# ELECTRONIC_LOAD.net
KiCad netlist of a schematic drawn in Altium Designer
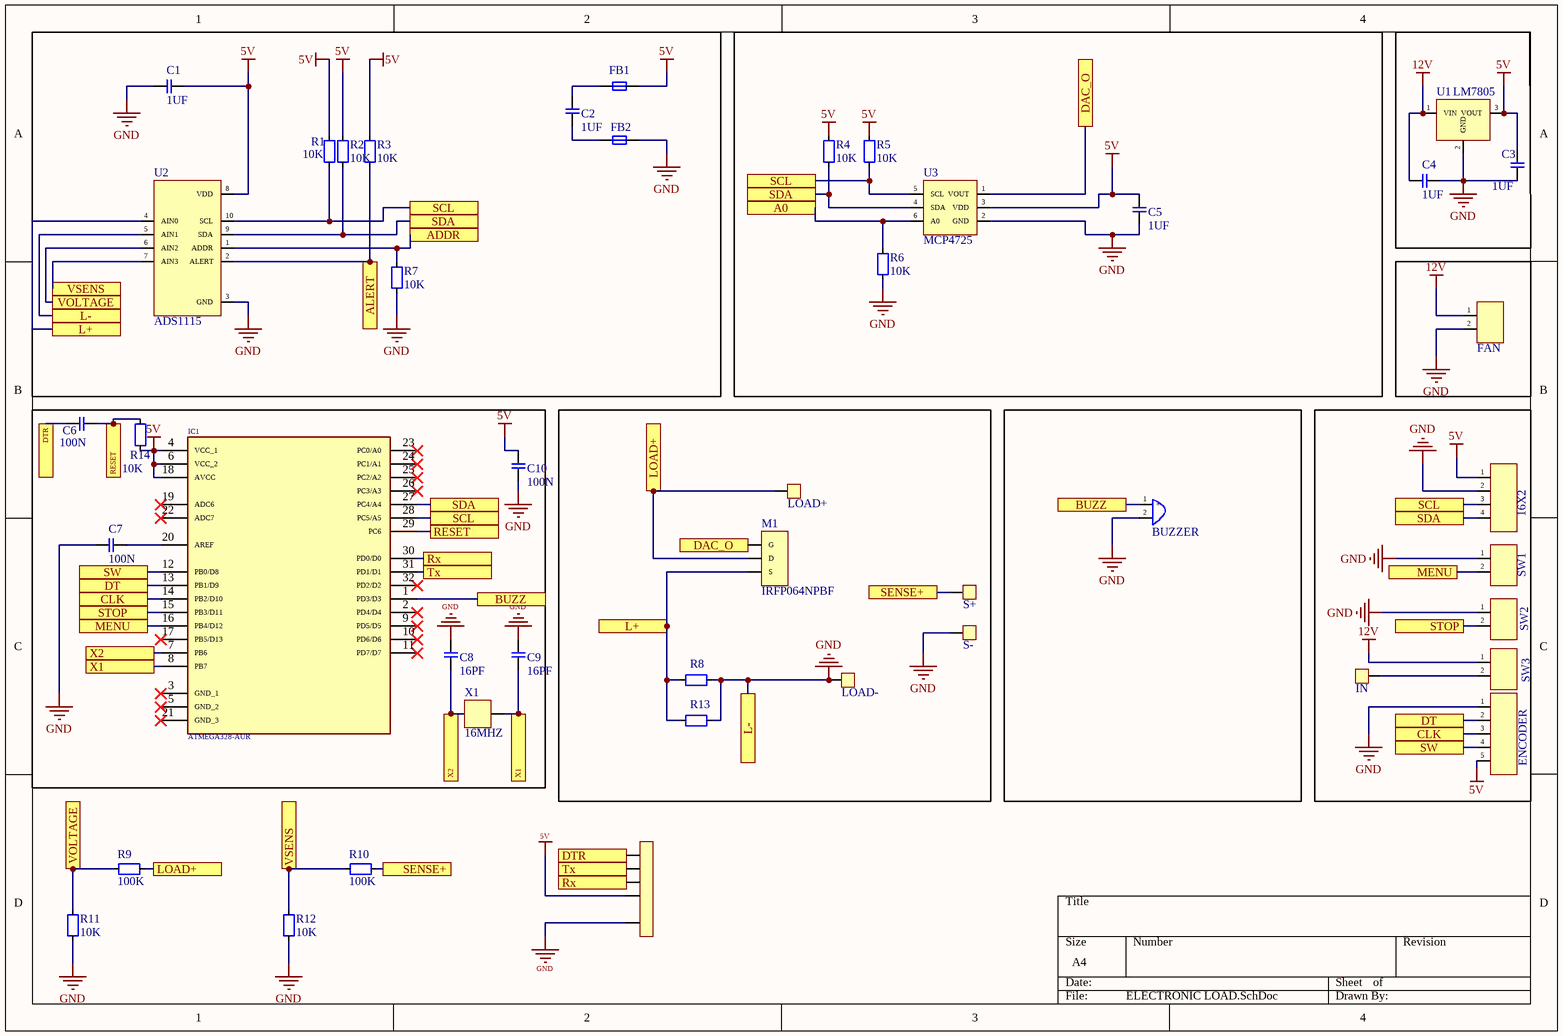
[diagram p0: ELECTRONIC LOAD.SchDoc]

(export (version "E")
  (design (tool "Eeschema 10.0.6"))
  (components
    (comp (ref "16X2") (value "16X2") (footprint "4PIN") (libsource (lib "ELECTRONIC LOAD") (part "4PIN")))
    (comp (ref "BUZZER")
      (value "BUZZER")
      (footprint "BUZZER")
      (description "YX-YT12075-YT03D")
      (libsource (lib "ELECTRONIC LOAD") (part "BUZZER"))
    )
    (comp (ref "C1")
      (value "1UF")
      (footprint "C-0805W")
      (description "0603 CAPACITOR")
      (libsource (lib "ELECTRONIC LOAD") (part "1UF CAPACITOR"))
    )
    (comp (ref "C2")
      (value "1UF")
      (footprint "C-0805W")
      (description "0603 CAPACITOR")
      (libsource (lib "ELECTRONIC LOAD") (part "1UF CAPACITOR"))
    )
    (comp (ref "C3")
      (value "1UF")
      (footprint "C-0805W")
      (description "0603 CAPACITOR")
      (libsource (lib "ELECTRONIC LOAD") (part "1UF CAPACITOR"))
    )
    (comp (ref "C4")
      (value "1UF")
      (footprint "C-0805W")
      (description "0603 CAPACITOR")
      (libsource (lib "ELECTRONIC LOAD") (part "1UF CAPACITOR"))
    )
    (comp (ref "C5")
      (value "1UF")
      (footprint "C-0805W")
      (description "0603 CAPACITOR")
      (libsource (lib "ELECTRONIC LOAD") (part "1UF CAPACITOR"))
    )
    (comp (ref "C6")
      (value "100N")
      (footprint "C-0805W")
      (libsource (lib "ELECTRONIC LOAD") (part "100N CAPACITOR"))
    )
    (comp (ref "C7")
      (value "100N")
      (footprint "C-0805W")
      (libsource (lib "ELECTRONIC LOAD") (part "100N CAPACITOR"))
    )
    (comp (ref "C8") (value "16PF") (footprint "C-0805W") (libsource (lib "ELECTRONIC LOAD") (part "16PF")))
    (comp (ref "C9") (value "16PF") (footprint "C-0805W") (libsource (lib "ELECTRONIC LOAD") (part "16PF")))
    (comp (ref "C10")
      (value "100N")
      (footprint "C-0805W")
      (libsource (lib "ELECTRONIC LOAD") (part "100N CAPACITOR"))
    )
    (comp (ref "ENCODER")
      (value "ENCODER")
      (footprint "5PIN")
      (libsource (lib "ELECTRONIC LOAD") (part "5PIN"))
    )
    (comp (ref "FAN") (value "SWITCH") (footprint "2PIN") (libsource (lib "ELECTRONIC LOAD") (part "2PIN")))
    (comp (ref "FB1")
      (value "FB")
      (footprint "R-0603W")
      (libsource (lib "ELECTRONIC LOAD") (part "LCB1608-152Y-N"))
    )
    (comp (ref "FB2")
      (value "FB")
      (footprint "R-0603W")
      (libsource (lib "ELECTRONIC LOAD") (part "LCB1608-152Y-N"))
    )
    (comp (ref "IC1")
      (value "ATMEGA328-AUR")
      (footprint "ATMEGA328")
      (fields (field (name "MOUSER PART NUMBER") "556-ATMEGA328-AUR"))
      (libsource (lib "ELECTRONIC LOAD") (part "ATMEGA328-AUR"))
    )
    (comp (ref "IN") (value "PAD") (footprint "PAD") (libsource (lib "") (part "PAD_1")))
    (comp (ref "LOAD+") (value "PAD") (footprint "PAD") (libsource (lib "ELECTRONIC LOAD") (part "PAD")))
    (comp (ref "LOAD-") (value "PAD") (footprint "PAD") (libsource (lib "ELECTRONIC LOAD") (part "PAD")))
    (comp (ref "M1")
      (value "IRFP064NPBF")
      (footprint "TO247")
      (description "TO247")
      (libsource (lib "ELECTRONIC LOAD") (part "IRFP064NPBF"))
    )
    (comp (ref "PIN") (value "PIN") (footprint "5PIN") (libsource (lib "ELECTRONIC LOAD") (part "PIN5")))
    (comp (ref "R1")
      (value "10K")
      (footprint "R-0805W")
      (libsource (lib "ELECTRONIC LOAD") (part "10K RESISTOR"))
    )
    (comp (ref "R2")
      (value "10K")
      (footprint "R-0805W")
      (libsource (lib "ELECTRONIC LOAD") (part "10K RESISTOR"))
    )
    (comp (ref "R3")
      (value "10K")
      (footprint "R-0805W")
      (libsource (lib "ELECTRONIC LOAD") (part "10K RESISTOR"))
    )
    (comp (ref "R4")
      (value "10K")
      (footprint "R-0805W")
      (libsource (lib "ELECTRONIC LOAD") (part "10K RESISTOR"))
    )
    (comp (ref "R5")
      (value "10K")
      (footprint "R-0805W")
      (libsource (lib "ELECTRONIC LOAD") (part "10K RESISTOR"))
    )
    (comp (ref "R6")
      (value "10K")
      (footprint "R-0805W")
      (libsource (lib "ELECTRONIC LOAD") (part "10K RESISTOR"))
    )
    (comp (ref "R7")
      (value "10K")
      (footprint "R-0805W")
      (libsource (lib "ELECTRONIC LOAD") (part "10K RESISTOR"))
    )
    (comp (ref "R8")
      (value "2512W")
      (footprint "R-2512W")
      (libsource (lib "ELECTRONIC LOAD") (part "2512W RESISTOR"))
    )
    (comp (ref "R9") (value "100K") (footprint "R-0805W") (libsource (lib "ELECTRONIC LOAD") (part "100K")))
    (comp (ref "R10") (value "100K") (footprint "R-0805W") (libsource (lib "ELECTRONIC LOAD") (part "100K")))
    (comp (ref "R11")
      (value "10K")
      (footprint "R-0805W")
      (libsource (lib "ELECTRONIC LOAD") (part "10K RESISTOR"))
    )
    (comp (ref "R12")
      (value "10K")
      (footprint "R-0805W")
      (libsource (lib "ELECTRONIC LOAD") (part "10K RESISTOR"))
    )
    (comp (ref "R13")
      (value "2512W")
      (footprint "R-2512W")
      (libsource (lib "ELECTRONIC LOAD") (part "2512W RESISTOR"))
    )
    (comp (ref "R14")
      (value "10K")
      (footprint "R-0805W")
      (libsource (lib "ELECTRONIC LOAD") (part "10K RESISTOR"))
    )
    (comp (ref "S+") (value "PAD") (footprint "PAD") (libsource (lib "ELECTRONIC LOAD") (part "PAD")))
    (comp (ref "S-") (value "PAD") (footprint "PAD") (libsource (lib "ELECTRONIC LOAD") (part "PAD")))
    (comp (ref "SW1") (value "SWITCH") (footprint "2PIN") (libsource (lib "ELECTRONIC LOAD") (part "2PIN")))
    (comp (ref "SW2") (value "SWITCH") (footprint "2PIN") (libsource (lib "ELECTRONIC LOAD") (part "2PIN")))
    (comp (ref "SW3") (value "SWITCH") (footprint "2PIN") (libsource (lib "ELECTRONIC LOAD") (part "2PIN")))
    (comp (ref "U1")
      (value "LM7805")
      (footprint "TO-252")
      (libsource (lib "ELECTRONIC LOAD") (part "LM7805"))
    )
    (comp (ref "U2")
      (value "ADS1115")
      (footprint "ADS1115")
      (libsource (lib "ELECTRONIC LOAD") (part "ADS1115"))
    )
    (comp (ref "U3")
      (value "MCP4725")
      (footprint "sot23-6")
      (description "SOT23-6")
      (libsource (lib "ELECTRONIC LOAD") (part "MCP4725"))
    )
    (comp (ref "X1")
      (value "16MHZ")
      (footprint "16MHZ CRYSTAL")
      (libsource (lib "ELECTRONIC LOAD") (part "16MHZ"))
    )
  )
  (nets
    (net (code "1") (name "/A0") (class "Default")
      (node (ref "R6") (pin "2") (pinfunction "2_2") (pintype "passive"))
      (node (ref "U3") (pin "6") (pinfunction "A0_6") (pintype "passive"))
    )
    (net (code "2") (name "/ADDR") (class "Default")
      (node (ref "R7") (pin "2") (pinfunction "2_2") (pintype "passive"))
      (node (ref "U2") (pin "1") (pinfunction "ADDR_1") (pintype "passive"))
    )
    (net (code "3") (name "/ALERT") (class "Default")
      (node (ref "R3") (pin "1") (pinfunction "1_1") (pintype "passive"))
      (node (ref "U2") (pin "2") (pinfunction "ALERT_2") (pintype "passive"))
    )
    (net (code "4") (name "/BUZZ") (class "Default")
      (node (ref "BUZZER") (pin "1") (pinfunction "+_1") (pintype "passive"))
      (node (ref "IC1") (pin "1") (pinfunction "PD3/D3_1") (pintype "passive"))
    )
    (net (code "5") (name "/CLK") (class "Default")
      (node (ref "ENCODER") (pin "3") (pinfunction "3_3") (pintype "passive"))
      (node (ref "IC1") (pin "14") (pinfunction "PB2/D10_14") (pintype "passive"))
    )
    (net (code "6") (name "/DAC_O") (class "Default")
      (node (ref "M1") (pin "1") (pinfunction "G_1") (pintype "passive"))
      (node (ref "U3") (pin "1") (pinfunction "VOUT_1") (pintype "passive"))
    )
    (net (code "7") (name "/DT") (class "Default")
      (node (ref "ENCODER") (pin "2") (pinfunction "2_2") (pintype "passive"))
      (node (ref "IC1") (pin "13") (pinfunction "PB1/D9_13") (pintype "passive"))
    )
    (net (code "8") (name "/DTR") (class "Default")
      (node (ref "C6") (pin "1") (pinfunction "1_1") (pintype "passive"))
      (node (ref "PIN") (pin "1") (pinfunction "1_1") (pintype "passive"))
    )
    (net (code "9") (name "/L+") (class "Default")
      (node (ref "M1") (pin "3") (pinfunction "S_3") (pintype "passive"))
      (node (ref "R13") (pin "1") (pinfunction "1_1") (pintype "passive"))
      (node (ref "R8") (pin "1") (pinfunction "1_1") (pintype "passive"))
      (node (ref "U2") (pin "4") (pinfunction "AIN0_4") (pintype "passive"))
    )
    (net (code "10") (name "/LOAD+") (class "Default")
      (node (ref "LOAD+") (pin "1") (pinfunction "1_1") (pintype "passive"))
      (node (ref "M1") (pin "2") (pinfunction "D_2") (pintype "passive"))
      (node (ref "R9") (pin "2") (pinfunction "2_2") (pintype "passive"))
    )
    (net (code "11") (name "/MENU") (class "Default")
      (node (ref "IC1") (pin "16") (pinfunction "PB4/D12_16") (pintype "passive"))
      (node (ref "SW1") (pin "2") (pinfunction "2_2") (pintype "passive"))
    )
    (net (code "12") (name "/RESET") (class "Default")
      (node (ref "C6") (pin "2") (pinfunction "2_2") (pintype "passive"))
      (node (ref "IC1") (pin "29") (pinfunction "PC6_29") (pintype "passive"))
      (node (ref "R14") (pin "1") (pinfunction "1_1") (pintype "passive"))
    )
    (net (code "13") (name "/Rx") (class "Default")
      (node (ref "IC1") (pin "30") (pinfunction "PD0/D0_30") (pintype "passive"))
      (node (ref "PIN") (pin "3") (pinfunction "3_3") (pintype "passive"))
    )
    (net (code "14") (name "/SCL") (class "Default")
      (node (ref "16X2") (pin "3") (pinfunction "3_3") (pintype "passive"))
      (node (ref "IC1") (pin "28") (pinfunction "PC5/A5_28") (pintype "passive"))
      (node (ref "R1") (pin "1") (pinfunction "1_1") (pintype "passive"))
      (node (ref "R5") (pin "1") (pinfunction "1_1") (pintype "passive"))
      (node (ref "U2") (pin "10") (pinfunction "SCL_10") (pintype "passive"))
      (node (ref "U3") (pin "5") (pinfunction "SCL_5") (pintype "passive"))
    )
    (net (code "15") (name "/SDA") (class "Default")
      (node (ref "16X2") (pin "4") (pinfunction "4_4") (pintype "passive"))
      (node (ref "IC1") (pin "27") (pinfunction "PC4/A4_27") (pintype "passive"))
      (node (ref "R2") (pin "1") (pinfunction "1_1") (pintype "passive"))
      (node (ref "R4") (pin "1") (pinfunction "1_1") (pintype "passive"))
      (node (ref "U2") (pin "9") (pinfunction "SDA_9") (pintype "passive"))
      (node (ref "U3") (pin "4") (pinfunction "SDA_4") (pintype "passive"))
    )
    (net (code "16") (name "/SENSE+") (class "Default")
      (node (ref "R10") (pin "2") (pinfunction "2_2") (pintype "passive"))
      (node (ref "S+") (pin "1") (pinfunction "1_1") (pintype "passive"))
    )
    (net (code "17") (name "/STOP") (class "Default")
      (node (ref "IC1") (pin "15") (pinfunction "PB3/D11_15") (pintype "passive"))
      (node (ref "SW2") (pin "2") (pinfunction "2_2") (pintype "passive"))
    )
    (net (code "18") (name "/SW") (class "Default")
      (node (ref "ENCODER") (pin "4") (pinfunction "4_4") (pintype "passive"))
      (node (ref "IC1") (pin "12") (pinfunction "PB0/D8_12") (pintype "passive"))
    )
    (net (code "19") (name "/Tx") (class "Default")
      (node (ref "IC1") (pin "31") (pinfunction "PD1/D1_31") (pintype "passive"))
      (node (ref "PIN") (pin "2") (pinfunction "2_2") (pintype "passive"))
    )
    (net (code "20") (name "/VOLTAGE") (class "Default")
      (node (ref "R11") (pin "2") (pinfunction "2_2") (pintype "passive"))
      (node (ref "R9") (pin "1") (pinfunction "1_1") (pintype "passive"))
      (node (ref "U2") (pin "6") (pinfunction "AIN2_6") (pintype "passive"))
    )
    (net (code "21") (name "/VSENS") (class "Default")
      (node (ref "R10") (pin "1") (pinfunction "1_1") (pintype "passive"))
      (node (ref "R12") (pin "2") (pinfunction "2_2") (pintype "passive"))
      (node (ref "U2") (pin "7") (pinfunction "AIN3_7") (pintype "passive"))
    )
    (net (code "22") (name "/X1") (class "Default")
      (node (ref "C9") (pin "1") (pinfunction "1_1") (pintype "passive"))
      (node (ref "IC1") (pin "8") (pinfunction "PB7_8") (pintype "passive"))
      (node (ref "X1") (pin "2") (pinfunction "2_2") (pintype "passive"))
    )
    (net (code "23") (name "/X2") (class "Default")
      (node (ref "C8") (pin "1") (pinfunction "1_1") (pintype "passive"))
      (node (ref "IC1") (pin "7") (pinfunction "PB6_7") (pintype "passive"))
      (node (ref "X1") (pin "1") (pinfunction "1_1") (pintype "passive"))
    )
    (net (code "24") (name "5V") (class "Default")
      (node (ref "16X2") (pin "1") (pinfunction "1_1") (pintype "passive"))
      (node (ref "C1") (pin "2") (pinfunction "2_2") (pintype "passive"))
      (node (ref "C10") (pin "2") (pinfunction "2_2") (pintype "passive"))
      (node (ref "C3") (pin "2") (pinfunction "2_2") (pintype "passive"))
      (node (ref "C5") (pin "2") (pinfunction "2_2") (pintype "passive"))
      (node (ref "ENCODER") (pin "5") (pinfunction "5_5") (pintype "passive"))
      (node (ref "FB1") (pin "2") (pinfunction "2_2") (pintype "passive"))
      (node (ref "IC1") (pin "18") (pinfunction "AVCC_18") (pintype "passive"))
      (node (ref "IC1") (pin "4") (pinfunction "VCC_1_4") (pintype "passive"))
      (node (ref "IC1") (pin "6") (pinfunction "VCC_2_6") (pintype "passive"))
      (node (ref "PIN") (pin "4") (pinfunction "4_4") (pintype "passive"))
      (node (ref "R1") (pin "2") (pinfunction "2_2") (pintype "passive"))
      (node (ref "R14") (pin "2") (pinfunction "2_2") (pintype "passive"))
      (node (ref "R2") (pin "2") (pinfunction "2_2") (pintype "passive"))
      (node (ref "R3") (pin "2") (pinfunction "2_2") (pintype "passive"))
      (node (ref "R4") (pin "2") (pinfunction "2_2") (pintype "passive"))
      (node (ref "R5") (pin "2") (pinfunction "2_2") (pintype "passive"))
      (node (ref "U1") (pin "3") (pinfunction "VOUT_3") (pintype "passive"))
      (node (ref "U2") (pin "8") (pinfunction "VDD_8") (pintype "passive"))
      (node (ref "U3") (pin "3") (pinfunction "VDD_3") (pintype "passive"))
    )
    (net (code "25") (name "12V") (class "Default")
      (node (ref "C4") (pin "1") (pinfunction "1_1") (pintype "passive"))
      (node (ref "FAN") (pin "1") (pinfunction "1_1") (pintype "passive"))
      (node (ref "SW3") (pin "1") (pinfunction "1_1") (pintype "passive"))
      (node (ref "U1") (pin "1") (pinfunction "VIN_1") (pintype "passive"))
    )
    (net (code "26") (name "GND") (class "Default")
      (node (ref "16X2") (pin "2") (pinfunction "2_2") (pintype "passive"))
      (node (ref "BUZZER") (pin "2") (pinfunction "-_2") (pintype "passive"))
      (node (ref "C1") (pin "1") (pinfunction "1_1") (pintype "passive"))
      (node (ref "C10") (pin "1") (pinfunction "1_1") (pintype "passive"))
      (node (ref "C3") (pin "1") (pinfunction "1_1") (pintype "passive"))
      (node (ref "C4") (pin "2") (pinfunction "2_2") (pintype "passive"))
      (node (ref "C5") (pin "1") (pinfunction "1_1") (pintype "passive"))
      (node (ref "C7") (pin "1") (pinfunction "1_1") (pintype "passive"))
      (node (ref "C8") (pin "2") (pinfunction "2_2") (pintype "passive"))
      (node (ref "C9") (pin "2") (pinfunction "2_2") (pintype "passive"))
      (node (ref "ENCODER") (pin "1") (pinfunction "1_1") (pintype "passive"))
      (node (ref "FAN") (pin "2") (pinfunction "2_2") (pintype "passive"))
      (node (ref "FB2") (pin "2") (pinfunction "2_2") (pintype "passive"))
      (node (ref "LOAD-") (pin "1") (pinfunction "1_1") (pintype "passive"))
      (node (ref "PIN") (pin "5") (pinfunction "5_5") (pintype "passive"))
      (node (ref "R11") (pin "1") (pinfunction "1_1") (pintype "passive"))
      (node (ref "R12") (pin "1") (pinfunction "1_1") (pintype "passive"))
      (node (ref "R13") (pin "2") (pinfunction "2_2") (pintype "passive"))
      (node (ref "R6") (pin "1") (pinfunction "1_1") (pintype "passive"))
      (node (ref "R7") (pin "1") (pinfunction "1_1") (pintype "passive"))
      (node (ref "R8") (pin "2") (pinfunction "2_2") (pintype "passive"))
      (node (ref "S-") (pin "1") (pinfunction "1_1") (pintype "passive"))
      (node (ref "SW1") (pin "1") (pinfunction "1_1") (pintype "passive"))
      (node (ref "SW2") (pin "1") (pinfunction "1_1") (pintype "passive"))
      (node (ref "U1") (pin "2") (pinfunction "GND_2") (pintype "passive"))
      (node (ref "U2") (pin "3") (pinfunction "GND_3") (pintype "passive"))
      (node (ref "U2") (pin "5") (pinfunction "AIN1_5") (pintype "passive"))
      (node (ref "U3") (pin "2") (pinfunction "GND_2") (pintype "passive"))
    )
    (net (code "27") (name "Net-(C2-Pad1)") (class "Default")
      (node (ref "C2") (pin "1") (pinfunction "1_1") (pintype "passive"))
      (node (ref "FB2") (pin "1") (pinfunction "1_1") (pintype "passive"))
    )
    (net (code "28") (name "Net-(C2-Pad2)") (class "Default")
      (node (ref "C2") (pin "2") (pinfunction "2_2") (pintype "passive"))
      (node (ref "FB1") (pin "1") (pinfunction "1_1") (pintype "passive"))
    )
    (net (code "29") (name "Net-(IC1-AREF)") (class "Default")
      (node (ref "C7") (pin "2") (pinfunction "2_2") (pintype "passive"))
      (node (ref "IC1") (pin "20") (pinfunction "AREF_20") (pintype "passive"))
    )
    (net (code "30") (name "Net-(IN-Pad1)") (class "Default")
      (node (ref "IN") (pin "1") (pinfunction "1_1") (pintype "passive"))
      (node (ref "SW3") (pin "2") (pinfunction "2_2") (pintype "passive"))
    )
    (net (code "31") (name "unconnected-(IC1-ADC6-Pad19)") (class "Default")
      (node (ref "IC1") (pin "19") (pinfunction "ADC6_19") (pintype "passive+no_connect"))
    )
    (net (code "32") (name "unconnected-(IC1-ADC7-Pad22)") (class "Default")
      (node (ref "IC1") (pin "22") (pinfunction "ADC7_22") (pintype "passive+no_connect"))
    )
    (net (code "33") (name "unconnected-(IC1-GND_1-Pad3)") (class "Default")
      (node (ref "IC1") (pin "3") (pinfunction "GND_1_3") (pintype "passive+no_connect"))
    )
    (net (code "34") (name "unconnected-(IC1-GND_2-Pad5)") (class "Default")
      (node (ref "IC1") (pin "5") (pinfunction "GND_2_5") (pintype "passive+no_connect"))
    )
    (net (code "35") (name "unconnected-(IC1-GND_3-Pad21)") (class "Default")
      (node (ref "IC1") (pin "21") (pinfunction "GND_3_21") (pintype "passive+no_connect"))
    )
    (net (code "36") (name "unconnected-(IC1-PB5{slash}D13-Pad17)") (class "Default")
      (node (ref "IC1") (pin "17") (pinfunction "PB5/D13_17") (pintype "passive+no_connect"))
    )
    (net (code "37") (name "unconnected-(IC1-PC0{slash}A0-Pad23)") (class "Default")
      (node (ref "IC1") (pin "23") (pinfunction "PC0/A0_23") (pintype "passive+no_connect"))
    )
    (net (code "38") (name "unconnected-(IC1-PC1{slash}A1-Pad24)") (class "Default")
      (node (ref "IC1") (pin "24") (pinfunction "PC1/A1_24") (pintype "passive+no_connect"))
    )
    (net (code "39") (name "unconnected-(IC1-PC2{slash}A2-Pad25)") (class "Default")
      (node (ref "IC1") (pin "25") (pinfunction "PC2/A2_25") (pintype "passive+no_connect"))
    )
    (net (code "40") (name "unconnected-(IC1-PC3{slash}A3-Pad26)") (class "Default")
      (node (ref "IC1") (pin "26") (pinfunction "PC3/A3_26") (pintype "passive+no_connect"))
    )
    (net (code "41") (name "unconnected-(IC1-PD2{slash}D2-Pad32)") (class "Default")
      (node (ref "IC1") (pin "32") (pinfunction "PD2/D2_32") (pintype "passive+no_connect"))
    )
    (net (code "42") (name "unconnected-(IC1-PD4{slash}D4-Pad2)") (class "Default")
      (node (ref "IC1") (pin "2") (pinfunction "PD4/D4_2") (pintype "passive+no_connect"))
    )
    (net (code "43") (name "unconnected-(IC1-PD5{slash}D5-Pad9)") (class "Default")
      (node (ref "IC1") (pin "9") (pinfunction "PD5/D5_9") (pintype "passive+no_connect"))
    )
    (net (code "44") (name "unconnected-(IC1-PD6{slash}D6-Pad10)") (class "Default")
      (node (ref "IC1") (pin "10") (pinfunction "PD6/D6_10") (pintype "passive+no_connect"))
    )
    (net (code "45") (name "unconnected-(IC1-PD7{slash}D7-Pad11)") (class "Default")
      (node (ref "IC1") (pin "11") (pinfunction "PD7/D7_11") (pintype "passive+no_connect"))
    )
  )
)
